# Adapter-CMRI8-3dot5mm-adapter.net
KiCad netlist of a schematic drawn in EAGLE
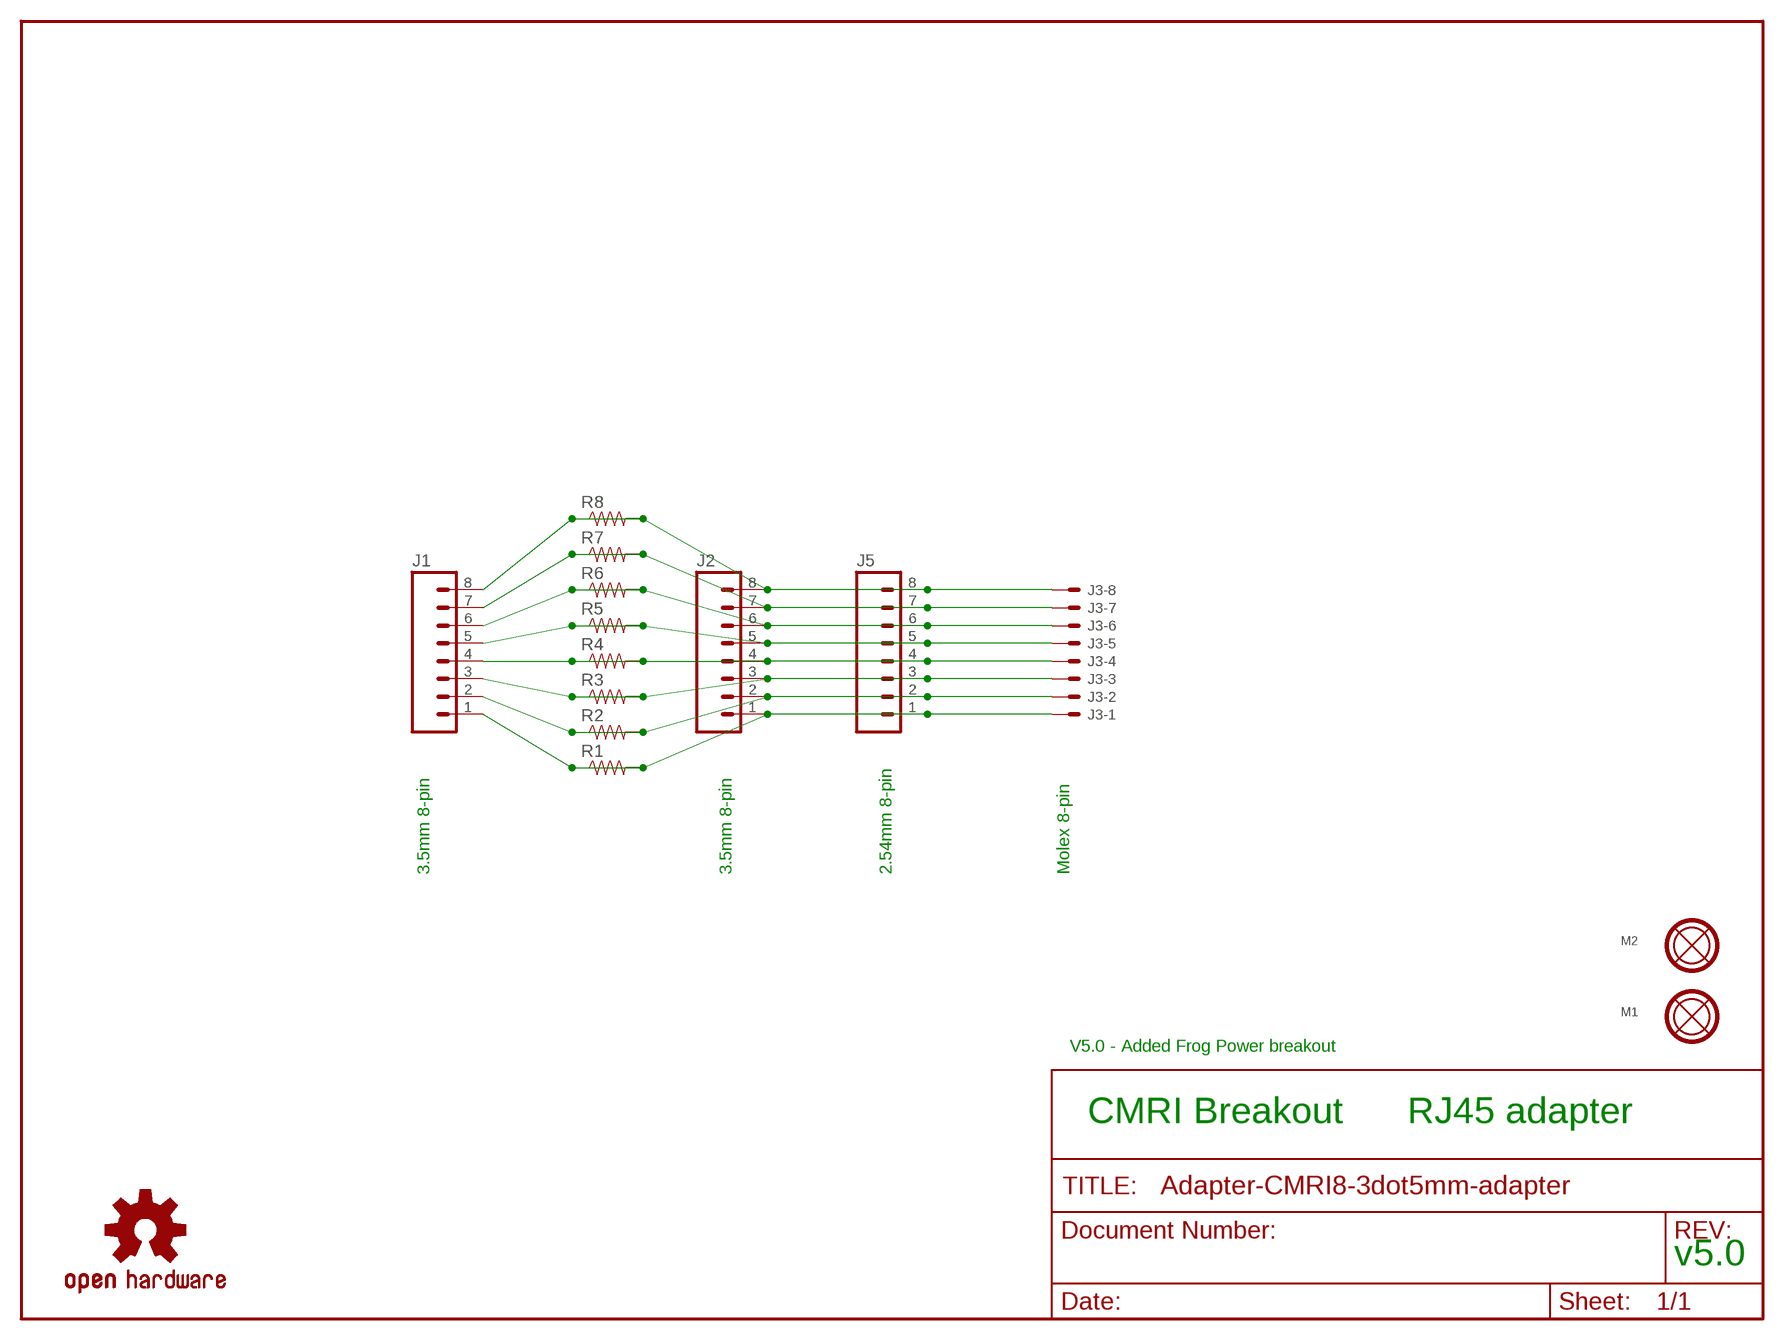
[diagram p0: schematic, sheet 1]

(export (version "E")
  (design (tool "Eeschema 10.0.6"))
  (components
    (comp (ref "J1")
      (value "CONNECTOR-M083.5MM-8")
      (footprint "eagle-import:SCREWTERMINAL-3.5MM-8")
      (libsource (lib "eagle-import") (part "CONNECTOR-M083.5MM-8"))
    )
    (comp (ref "J2")
      (value "CONNECTOR-M083.5MM-8")
      (footprint "eagle-import:SCREWTERMINAL-3.5MM-8")
      (libsource (lib "eagle-import") (part "CONNECTOR-M083.5MM-8"))
    )
    (comp (ref "J3")
      (value "KK-156-8F")
      (footprint "eagle-import:KK-156-8-F")
      (libsource (lib "eagle-import") (part "KK-156-8F"))
    )
    (comp (ref "J5")
      (value "CONNECTOR-M08LOCK")
      (footprint "eagle-import:1X08_LOCK")
      (libsource (lib "eagle-import") (part "CONNECTOR-M08LOCK"))
    )
    (comp (ref "M1")
      (value "MOUNTINGHOLE")
      (footprint "eagle-import:MOUNTINGHOLE")
      (libsource (lib "eagle-import") (part "MOUNTINGHOLE"))
    )
    (comp (ref "M2")
      (value "MOUNTINGHOLE")
      (footprint "eagle-import:MOUNTINGHOLE")
      (libsource (lib "eagle-import") (part "MOUNTINGHOLE"))
    )
    (comp (ref "R1")
      (value "RPTH04")
      (footprint "eagle-import:AXIAL-0.4-RES")
      (libsource (lib "eagle-import") (part "RPTH04"))
    )
    (comp (ref "R2")
      (value "RPTH04")
      (footprint "eagle-import:AXIAL-0.4-RES")
      (libsource (lib "eagle-import") (part "RPTH04"))
    )
    (comp (ref "R3")
      (value "RPTH04")
      (footprint "eagle-import:AXIAL-0.4-RES")
      (libsource (lib "eagle-import") (part "RPTH04"))
    )
    (comp (ref "R4")
      (value "RPTH04")
      (footprint "eagle-import:AXIAL-0.4-RES")
      (libsource (lib "eagle-import") (part "RPTH04"))
    )
    (comp (ref "R5")
      (value "RPTH04")
      (footprint "eagle-import:AXIAL-0.4-RES")
      (libsource (lib "eagle-import") (part "RPTH04"))
    )
    (comp (ref "R6")
      (value "RPTH04")
      (footprint "eagle-import:AXIAL-0.4-RES")
      (libsource (lib "eagle-import") (part "RPTH04"))
    )
    (comp (ref "R7")
      (value "RPTH04")
      (footprint "eagle-import:AXIAL-0.4-RES")
      (libsource (lib "eagle-import") (part "RPTH04"))
    )
    (comp (ref "R8")
      (value "RPTH04")
      (footprint "eagle-import:AXIAL-0.4-RES")
      (libsource (lib "eagle-import") (part "RPTH04"))
    )
    (comp (ref "U$1")
      (value "DOC-OSHW-LOGO-L")
      (footprint "eagle-import:OSHW-LOGO-L")
      (libsource (lib "eagle-import") (part "DOC-OSHW-LOGO-L"))
    )
  )
  (nets
    (net (code "1") (name "Net-(J3A-S)") (class "Default")
      (node (ref "J1") (pin "1") (pinfunction "1_1") (pintype "passive"))
      (node (ref "J2") (pin "1") (pinfunction "1_1") (pintype "passive"))
      (node (ref "J3") (pin "1") (pinfunction "S_1") (pintype "passive"))
      (node (ref "J5") (pin "1") (pinfunction "1_1") (pintype "passive"))
      (node (ref "R1") (pin "P$1") (pinfunction "1_P$1") (pintype "passive"))
      (node (ref "R1") (pin "P$2") (pinfunction "2_P$2") (pintype "passive"))
    )
    (net (code "2") (name "Net-(J3B-S)") (class "Default")
      (node (ref "J1") (pin "2") (pinfunction "2_2") (pintype "passive"))
      (node (ref "J2") (pin "2") (pinfunction "2_2") (pintype "passive"))
      (node (ref "J3") (pin "2") (pinfunction "S_2") (pintype "passive"))
      (node (ref "J5") (pin "2") (pinfunction "2_2") (pintype "passive"))
      (node (ref "R2") (pin "P$1") (pinfunction "1_P$1") (pintype "passive"))
      (node (ref "R2") (pin "P$2") (pinfunction "2_P$2") (pintype "passive"))
    )
    (net (code "3") (name "Net-(J3C-S)") (class "Default")
      (node (ref "J1") (pin "3") (pinfunction "3_3") (pintype "passive"))
      (node (ref "J2") (pin "3") (pinfunction "3_3") (pintype "passive"))
      (node (ref "J3") (pin "3") (pinfunction "S_3") (pintype "passive"))
      (node (ref "J5") (pin "3") (pinfunction "3_3") (pintype "passive"))
      (node (ref "R3") (pin "P$1") (pinfunction "1_P$1") (pintype "passive"))
      (node (ref "R3") (pin "P$2") (pinfunction "2_P$2") (pintype "passive"))
    )
    (net (code "4") (name "Net-(J3D-S)") (class "Default")
      (node (ref "J1") (pin "4") (pinfunction "4_4") (pintype "passive"))
      (node (ref "J2") (pin "4") (pinfunction "4_4") (pintype "passive"))
      (node (ref "J3") (pin "4") (pinfunction "S_4") (pintype "passive"))
      (node (ref "J5") (pin "4") (pinfunction "4_4") (pintype "passive"))
      (node (ref "R4") (pin "P$1") (pinfunction "1_P$1") (pintype "passive"))
      (node (ref "R4") (pin "P$2") (pinfunction "2_P$2") (pintype "passive"))
    )
    (net (code "5") (name "Net-(J3E-S)") (class "Default")
      (node (ref "J1") (pin "5") (pinfunction "5_5") (pintype "passive"))
      (node (ref "J2") (pin "5") (pinfunction "5_5") (pintype "passive"))
      (node (ref "J3") (pin "5") (pinfunction "S_5") (pintype "passive"))
      (node (ref "J5") (pin "5") (pinfunction "5_5") (pintype "passive"))
      (node (ref "R5") (pin "P$1") (pinfunction "1_P$1") (pintype "passive"))
      (node (ref "R5") (pin "P$2") (pinfunction "2_P$2") (pintype "passive"))
    )
    (net (code "6") (name "Net-(J3F-S)") (class "Default")
      (node (ref "J1") (pin "6") (pinfunction "6_6") (pintype "passive"))
      (node (ref "J2") (pin "6") (pinfunction "6_6") (pintype "passive"))
      (node (ref "J3") (pin "6") (pinfunction "S_6") (pintype "passive"))
      (node (ref "J5") (pin "6") (pinfunction "6_6") (pintype "passive"))
      (node (ref "R6") (pin "P$1") (pinfunction "1_P$1") (pintype "passive"))
      (node (ref "R6") (pin "P$2") (pinfunction "2_P$2") (pintype "passive"))
    )
    (net (code "7") (name "Net-(J3G-S)") (class "Default")
      (node (ref "J1") (pin "7") (pinfunction "7_7") (pintype "passive"))
      (node (ref "J2") (pin "7") (pinfunction "7_7") (pintype "passive"))
      (node (ref "J3") (pin "7") (pinfunction "S_7") (pintype "passive"))
      (node (ref "J5") (pin "7") (pinfunction "7_7") (pintype "passive"))
      (node (ref "R7") (pin "P$1") (pinfunction "1_P$1") (pintype "passive"))
      (node (ref "R7") (pin "P$2") (pinfunction "2_P$2") (pintype "passive"))
    )
    (net (code "8") (name "Net-(J3H-S)") (class "Default")
      (node (ref "J1") (pin "8") (pinfunction "8_8") (pintype "passive"))
      (node (ref "J2") (pin "8") (pinfunction "8_8") (pintype "passive"))
      (node (ref "J3") (pin "8") (pinfunction "S_8") (pintype "passive"))
      (node (ref "J5") (pin "8") (pinfunction "8_8") (pintype "passive"))
      (node (ref "R8") (pin "P$1") (pinfunction "1_P$1") (pintype "passive"))
      (node (ref "R8") (pin "P$2") (pinfunction "2_P$2") (pintype "passive"))
    )
  )
)
